# ESP8266.net
KiCad netlist of a schematic drawn in Altium Designer
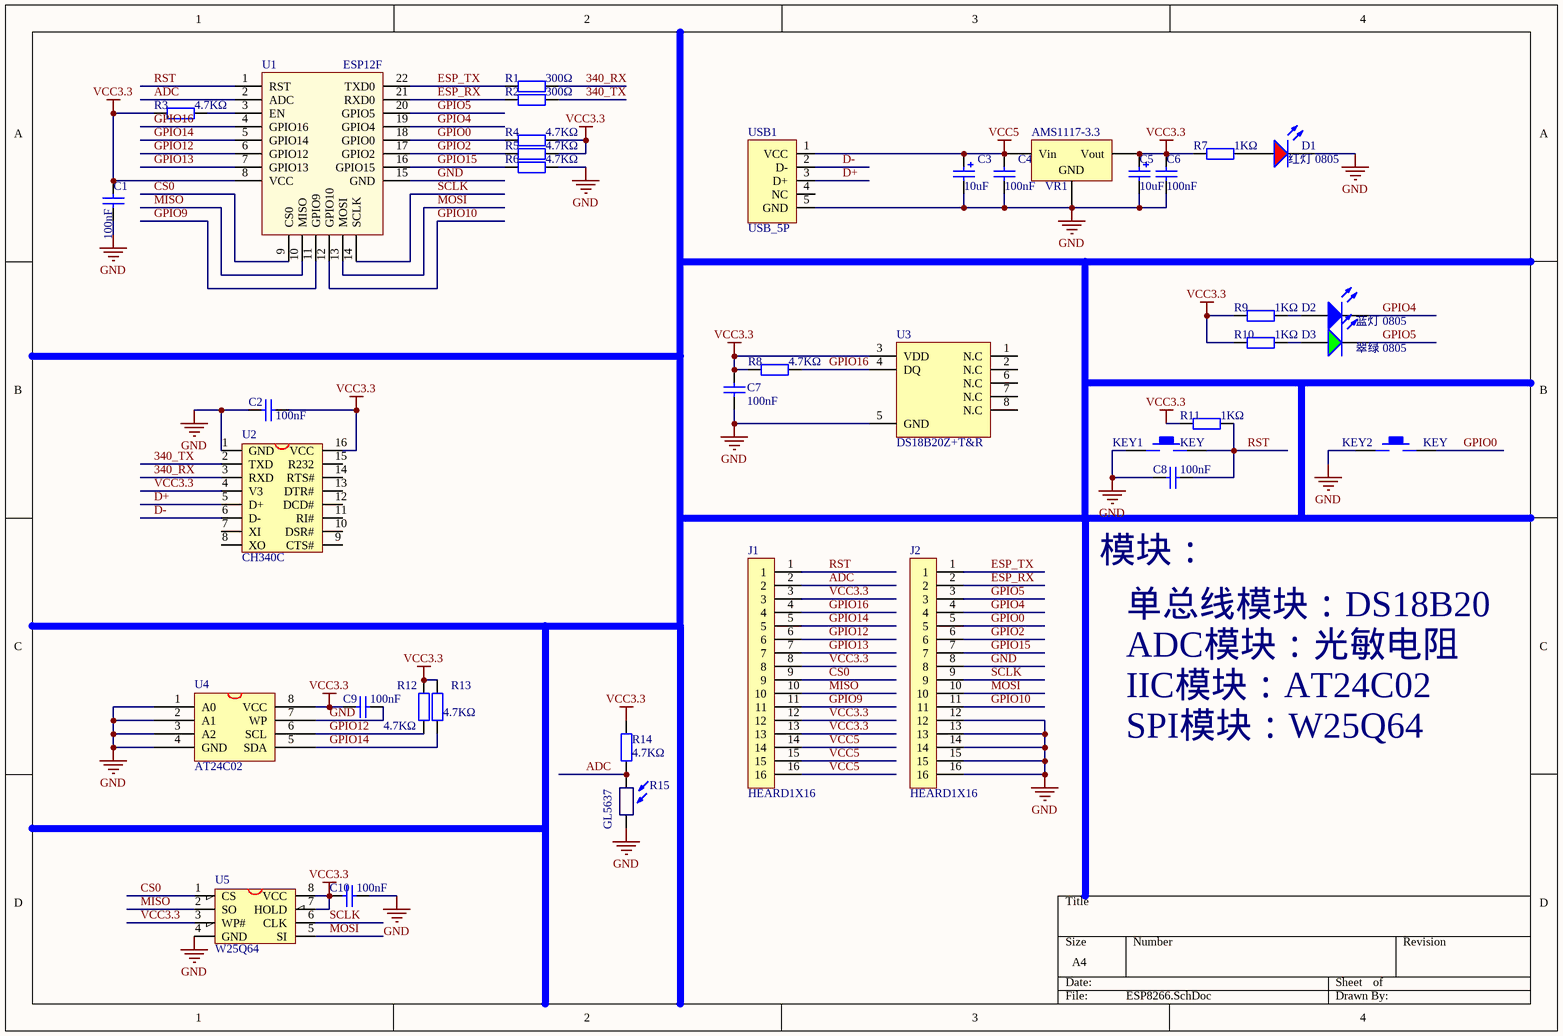
[diagram p0: ESP8266.SchDoc]

(export (version "E")
  (design (tool "Eeschema 10.0.6"))
  (components
    (comp (ref "C1")
      (value "100nF")
      (footprint "LC-0805_C")
      (description "贴片电容")
      (libsource (lib "Miscellaneous Devices LC") (part "0805 100nF(104) 10% 50V"))
    )
    (comp (ref "C2")
      (value "100nF")
      (footprint "LC-0805_C")
      (description "贴片电容")
      (libsource (lib "Miscellaneous Devices LC") (part "0805 100nF(104) 10% 50V"))
    )
    (comp (ref "C3")
      (value "10uF")
      (footprint "LC-CASE-A_3216")
      (description "钽电容")
      (libsource (lib "Miscellaneous Devices LC") (part "3216 10uF (106) 10% 16V"))
    )
    (comp (ref "C4")
      (value "100nF")
      (footprint "LC-0805_C")
      (description "贴片电容")
      (libsource (lib "Miscellaneous Devices LC") (part "0805 100nF(104) 10% 50V"))
    )
    (comp (ref "C5")
      (value "10uF")
      (footprint "LC-CASE-A_3216")
      (description "钽电容")
      (libsource (lib "Miscellaneous Devices LC") (part "3216 10uF (106) 10% 16V"))
    )
    (comp (ref "C6")
      (value "100nF")
      (footprint "LC-0805_C")
      (description "贴片电容")
      (libsource (lib "Miscellaneous Devices LC") (part "0805 100nF(104) 10% 50V"))
    )
    (comp (ref "C7")
      (value "100nF")
      (footprint "LC-0805_C")
      (description "贴片电容")
      (libsource (lib "Miscellaneous Devices LC") (part "0805 100nF(104) 10% 50V"))
    )
    (comp (ref "C8")
      (value "100nF")
      (footprint "LC-0805_C")
      (description "贴片电容")
      (libsource (lib "Miscellaneous Devices LC") (part "0805 100nF(104) 10% 50V"))
    )
    (comp (ref "C9")
      (value "100nF")
      (footprint "LC-0805_C")
      (description "贴片电容")
      (libsource (lib "Miscellaneous Devices LC") (part "0805 100nF(104) 10% 50V"))
    )
    (comp (ref "C10")
      (value "100nF")
      (footprint "LC-0805_C")
      (description "贴片电容")
      (libsource (lib "Miscellaneous Devices LC") (part "0805 100nF(104) 10% 50V"))
    )
    (comp (ref "D1")
      (value "红灯 0805")
      (footprint "LC-0805_LED_S1")
      (description "发光二极管")
      (libsource (lib "Miscellaneous Devices LC") (part "0805 红灯"))
    )
    (comp (ref "D2")
      (value "蓝灯 0805")
      (footprint "LC-0805_LED_S1")
      (description "发光二极管")
      (libsource (lib "Miscellaneous Devices LC") (part "0805 蓝灯"))
    )
    (comp (ref "D3")
      (value "翠绿 0805")
      (footprint "LC-0805_LED_S1")
      (description "发光二极管")
      (libsource (lib "Miscellaneous Devices LC") (part "0805 翠绿"))
    )
    (comp (ref "J1") (value "HEARD1X16") (footprint "HDR1X16") (libsource (lib "ESP8266") (part "HEARD1X16")))
    (comp (ref "J2") (value "HEARD1X16") (footprint "HDR1X16") (libsource (lib "ESP8266") (part "HEARD1X16")))
    (comp (ref "KEY1") (value "KEY") (footprint "KEY_直插_6*6") (libsource (lib "ESP8266") (part "KEY")))
    (comp (ref "KEY2") (value "KEY") (footprint "KEY_直插_6*6") (libsource (lib "ESP8266") (part "KEY")))
    (comp (ref "R1")
      (value "300Ω")
      (footprint "LC-0805_R")
      (description "贴片电阻")
      (libsource (lib "Miscellaneous Devices LC") (part "0805 4.7KΩ (4701) 1%"))
    )
    (comp (ref "R2")
      (value "300Ω")
      (footprint "LC-0805_R")
      (description "贴片电阻")
      (libsource (lib "Miscellaneous Devices LC") (part "0805 4.7KΩ (4701) 1%"))
    )
    (comp (ref "R3")
      (value "4.7KΩ")
      (footprint "LC-0805_R")
      (description "贴片电阻")
      (libsource (lib "Miscellaneous Devices LC") (part "0805 4.7KΩ (4701) 1%"))
    )
    (comp (ref "R4")
      (value "4.7KΩ")
      (footprint "LC-0805_R")
      (description "贴片电阻")
      (libsource (lib "Miscellaneous Devices LC") (part "0805 4.7KΩ (4701) 1%"))
    )
    (comp (ref "R5")
      (value "4.7KΩ")
      (footprint "LC-0805_R")
      (description "贴片电阻")
      (libsource (lib "Miscellaneous Devices LC") (part "0805 4.7KΩ (4701) 1%"))
    )
    (comp (ref "R6")
      (value "4.7KΩ")
      (footprint "LC-0805_R")
      (description "贴片电阻")
      (libsource (lib "Miscellaneous Devices LC") (part "0805 4.7KΩ (4701) 1%"))
    )
    (comp (ref "R7")
      (value "1KΩ")
      (footprint "LC-0805_R")
      (description "贴片电阻")
      (libsource (lib "Miscellaneous Devices LC") (part "0805 1KΩ (1001) 1%"))
    )
    (comp (ref "R8")
      (value "4.7KΩ")
      (footprint "LC-0805_R")
      (description "贴片电阻")
      (libsource (lib "Miscellaneous Devices LC") (part "0805 4.7KΩ (4701) 1%"))
    )
    (comp (ref "R9")
      (value "1KΩ")
      (footprint "LC-0805_R")
      (description "贴片电阻")
      (libsource (lib "Miscellaneous Devices LC") (part "0805 1KΩ (1001) 1%"))
    )
    (comp (ref "R10")
      (value "1KΩ")
      (footprint "LC-0805_R")
      (description "贴片电阻")
      (libsource (lib "Miscellaneous Devices LC") (part "0805 1KΩ (1001) 1%"))
    )
    (comp (ref "R11")
      (value "1KΩ")
      (footprint "LC-0805_R")
      (description "贴片电阻")
      (libsource (lib "Miscellaneous Devices LC") (part "0805 1KΩ (1001) 1%"))
    )
    (comp (ref "R12")
      (value "4.7KΩ")
      (footprint "LC-0805_R")
      (description "贴片电阻")
      (libsource (lib "") (part "0805 4.7KΩ (4701) 1%_1"))
    )
    (comp (ref "R13")
      (value "4.7KΩ")
      (footprint "LC-0805_R")
      (description "贴片电阻")
      (libsource (lib "") (part "0805 4.7KΩ (4701) 1%_1"))
    )
    (comp (ref "R14")
      (value "4.7KΩ")
      (footprint "LC-0805_R")
      (description "贴片电阻")
      (libsource (lib "") (part "0805 4.7KΩ (4701) 1%_1"))
    )
    (comp (ref "R15") (value "GL5637") (footprint "Through Hole") (libsource (lib "ESP8266") (part "GL5637")))
    (comp (ref "U1") (value "ESP12F") (footprint "ESP6266") (libsource (lib "ESP8266") (part "ESP8266")))
    (comp (ref "U2") (value "CH340C") (footprint "SOIC-16_150MIL") (libsource (lib "ESP8266") (part "CH340")))
    (comp (ref "U3")
      (value "DS18B20Z+T&R")
      (footprint "SOIC-8_150mil")
      (libsource (lib "ESP8266") (part "DS18B20Z+T&R"))
    )
    (comp (ref "U4")
      (value "AT24C02")
      (footprint "SOIC-8_150mil")
      (libsource (lib "ESP8266") (part "AT24C02"))
    )
    (comp (ref "U5") (value "W25Q64") (footprint "SOIC-8_208MIL") (libsource (lib "ESP8266") (part "W25Q64")))
    (comp (ref "USB1") (value "USB_5P") (footprint "USB_5P") (libsource (lib "ESP8266") (part "USB_5P")))
    (comp (ref "VR1")
      (value "AMS1117-3.3")
      (footprint "LC-SOT-223")
      (description "低压差线性稳压(LDO)")
      (libsource (lib "Miscellaneous Devices LC") (part "SOT-223 AMS1117-3.3"))
    )
  )
  (nets
    (net (code "1") (name "/340_RX") (class "Default")
      (node (ref "R1") (pin "2") (pinfunction "2_2") (pintype "passive"))
      (node (ref "U2") (pin "3") (pinfunction "RXD_3") (pintype "passive"))
    )
    (net (code "2") (name "/340_TX") (class "Default")
      (node (ref "R2") (pin "2") (pinfunction "2_2") (pintype "passive"))
      (node (ref "U2") (pin "2") (pinfunction "TXD_2") (pintype "passive"))
    )
    (net (code "3") (name "/ADC") (class "Default")
      (node (ref "J1") (pin "2") (pinfunction "2_2") (pintype "passive"))
      (node (ref "R14") (pin "1") (pinfunction "1_1") (pintype "passive"))
      (node (ref "R15") (pin "1") (pinfunction "1_1") (pintype "passive"))
      (node (ref "U1") (pin "2") (pinfunction "ADC_2") (pintype "passive"))
    )
    (net (code "4") (name "/CS0") (class "Default")
      (node (ref "J1") (pin "9") (pinfunction "9_9") (pintype "passive"))
      (node (ref "U1") (pin "9") (pinfunction "CS0_9") (pintype "passive"))
      (node (ref "U5") (pin "1") (pinfunction "CS_1") (pintype "passive"))
    )
    (net (code "5") (name "/D+") (class "Default")
      (node (ref "U2") (pin "5") (pinfunction "D+_5") (pintype "passive"))
      (node (ref "USB1") (pin "3") (pinfunction "D+_3") (pintype "passive"))
    )
    (net (code "6") (name "/D-") (class "Default")
      (node (ref "U2") (pin "6") (pinfunction "D-_6") (pintype "passive"))
      (node (ref "USB1") (pin "2") (pinfunction "D-_2") (pintype "passive"))
    )
    (net (code "7") (name "/ESP_RX") (class "Default")
      (node (ref "J2") (pin "2") (pinfunction "2_2") (pintype "passive"))
      (node (ref "R2") (pin "1") (pinfunction "1_1") (pintype "passive"))
      (node (ref "U1") (pin "21") (pinfunction "RXD0_21") (pintype "passive"))
    )
    (net (code "8") (name "/ESP_TX") (class "Default")
      (node (ref "J2") (pin "1") (pinfunction "1_1") (pintype "passive"))
      (node (ref "R1") (pin "1") (pinfunction "1_1") (pintype "passive"))
      (node (ref "U1") (pin "22") (pinfunction "TXD0_22") (pintype "passive"))
    )
    (net (code "9") (name "/GPIO0") (class "Default")
      (node (ref "J2") (pin "5") (pinfunction "5_5") (pintype "passive"))
      (node (ref "KEY2") (pin "2") (pinfunction "2_2") (pintype "passive"))
      (node (ref "R4") (pin "1") (pinfunction "1_1") (pintype "passive"))
      (node (ref "U1") (pin "18") (pinfunction "GPIO0_18") (pintype "passive"))
    )
    (net (code "10") (name "/GPIO2") (class "Default")
      (node (ref "J2") (pin "6") (pinfunction "6_6") (pintype "passive"))
      (node (ref "R5") (pin "1") (pinfunction "1_1") (pintype "passive"))
      (node (ref "U1") (pin "17") (pinfunction "GPIO2_17") (pintype "passive"))
    )
    (net (code "11") (name "/GPIO4") (class "Default")
      (node (ref "D2") (pin "K") (pinfunction "K_K") (pintype "passive"))
      (node (ref "J2") (pin "4") (pinfunction "4_4") (pintype "passive"))
      (node (ref "U1") (pin "19") (pinfunction "GPIO4_19") (pintype "passive"))
    )
    (net (code "12") (name "/GPIO5") (class "Default")
      (node (ref "D3") (pin "K") (pinfunction "K_K") (pintype "passive"))
      (node (ref "J2") (pin "3") (pinfunction "3_3") (pintype "passive"))
      (node (ref "U1") (pin "20") (pinfunction "GPIO5_20") (pintype "passive"))
    )
    (net (code "13") (name "/GPIO9") (class "Default")
      (node (ref "J1") (pin "11") (pinfunction "11_11") (pintype "passive"))
      (node (ref "U1") (pin "11") (pinfunction "GPIO9_11") (pintype "passive"))
    )
    (net (code "14") (name "/GPIO10") (class "Default")
      (node (ref "J2") (pin "11") (pinfunction "11_11") (pintype "passive"))
      (node (ref "U1") (pin "12") (pinfunction "GPIO10_12") (pintype "passive"))
    )
    (net (code "15") (name "/GPIO12") (class "Default")
      (node (ref "J1") (pin "6") (pinfunction "6_6") (pintype "passive"))
      (node (ref "R12") (pin "1") (pinfunction "1_1") (pintype "passive"))
      (node (ref "U1") (pin "6") (pinfunction "GPIO12_6") (pintype "passive"))
      (node (ref "U4") (pin "6") (pinfunction "SCL_6") (pintype "passive"))
    )
    (net (code "16") (name "/GPIO13") (class "Default")
      (node (ref "J1") (pin "7") (pinfunction "7_7") (pintype "passive"))
      (node (ref "U1") (pin "7") (pinfunction "GPIO13_7") (pintype "passive"))
    )
    (net (code "17") (name "/GPIO14") (class "Default")
      (node (ref "J1") (pin "5") (pinfunction "5_5") (pintype "passive"))
      (node (ref "R13") (pin "1") (pinfunction "1_1") (pintype "passive"))
      (node (ref "U1") (pin "5") (pinfunction "GPIO14_5") (pintype "passive"))
      (node (ref "U4") (pin "5") (pinfunction "SDA_5") (pintype "passive"))
    )
    (net (code "18") (name "/GPIO15") (class "Default")
      (node (ref "J2") (pin "7") (pinfunction "7_7") (pintype "passive"))
      (node (ref "R6") (pin "1") (pinfunction "1_1") (pintype "passive"))
      (node (ref "U1") (pin "16") (pinfunction "GPIO15_16") (pintype "passive"))
    )
    (net (code "19") (name "/GPIO16") (class "Default")
      (node (ref "J1") (pin "4") (pinfunction "4_4") (pintype "passive"))
      (node (ref "R8") (pin "2") (pinfunction "2_2") (pintype "passive"))
      (node (ref "U1") (pin "4") (pinfunction "GPIO16_4") (pintype "passive"))
      (node (ref "U3") (pin "4") (pinfunction "DQ_4") (pintype "passive"))
    )
    (net (code "20") (name "/MISO") (class "Default")
      (node (ref "J1") (pin "10") (pinfunction "10_10") (pintype "passive"))
      (node (ref "U1") (pin "10") (pinfunction "MISO_10") (pintype "passive"))
      (node (ref "U5") (pin "2") (pinfunction "SO_2") (pintype "passive"))
    )
    (net (code "21") (name "/MOSI") (class "Default")
      (node (ref "J2") (pin "10") (pinfunction "10_10") (pintype "passive"))
      (node (ref "U1") (pin "13") (pinfunction "MOSI_13") (pintype "passive"))
      (node (ref "U5") (pin "5") (pinfunction "SI_5") (pintype "passive"))
    )
    (net (code "22") (name "/RST") (class "Default")
      (node (ref "C8") (pin "2") (pinfunction "2_2") (pintype "passive"))
      (node (ref "J1") (pin "1") (pinfunction "1_1") (pintype "passive"))
      (node (ref "KEY1") (pin "2") (pinfunction "2_2") (pintype "passive"))
      (node (ref "R11") (pin "2") (pinfunction "2_2") (pintype "passive"))
      (node (ref "U1") (pin "1") (pinfunction "RST_1") (pintype "passive"))
    )
    (net (code "23") (name "/SCLK") (class "Default")
      (node (ref "J2") (pin "9") (pinfunction "9_9") (pintype "passive"))
      (node (ref "U1") (pin "14") (pinfunction "SCLK_14") (pintype "passive"))
      (node (ref "U5") (pin "6") (pinfunction "CLK_6") (pintype "passive"))
    )
    (net (code "24") (name "GND") (class "Default")
      (node (ref "C1") (pin "1") (pinfunction "1_1") (pintype "passive"))
      (node (ref "C10") (pin "2") (pinfunction "2_2") (pintype "passive"))
      (node (ref "C2") (pin "1") (pinfunction "1_1") (pintype "passive"))
      (node (ref "C3") (pin "2") (pinfunction "2_2") (pintype "passive"))
      (node (ref "C4") (pin "1") (pinfunction "1_1") (pintype "passive"))
      (node (ref "C5") (pin "2") (pinfunction "2_2") (pintype "passive"))
      (node (ref "C6") (pin "1") (pinfunction "1_1") (pintype "passive"))
      (node (ref "C7") (pin "1") (pinfunction "1_1") (pintype "passive"))
      (node (ref "C8") (pin "1") (pinfunction "1_1") (pintype "passive"))
      (node (ref "C9") (pin "2") (pinfunction "2_2") (pintype "passive"))
      (node (ref "D1") (pin "K") (pinfunction "K_K") (pintype "passive"))
      (node (ref "J2") (pin "12") (pinfunction "12_12") (pintype "passive"))
      (node (ref "J2") (pin "13") (pinfunction "13_13") (pintype "passive"))
      (node (ref "J2") (pin "14") (pinfunction "14_14") (pintype "passive"))
      (node (ref "J2") (pin "15") (pinfunction "15_15") (pintype "passive"))
      (node (ref "J2") (pin "16") (pinfunction "16_16") (pintype "passive"))
      (node (ref "J2") (pin "8") (pinfunction "8_8") (pintype "passive"))
      (node (ref "KEY1") (pin "1") (pinfunction "1_1") (pintype "passive"))
      (node (ref "KEY2") (pin "1") (pinfunction "1_1") (pintype "passive"))
      (node (ref "R15") (pin "2") (pinfunction "2_2") (pintype "passive"))
      (node (ref "R6") (pin "2") (pinfunction "2_2") (pintype "passive"))
      (node (ref "U1") (pin "15") (pinfunction "GND_15") (pintype "passive"))
      (node (ref "U2") (pin "1") (pinfunction "GND_1") (pintype "passive"))
      (node (ref "U3") (pin "5") (pinfunction "GND_5") (pintype "passive"))
      (node (ref "U4") (pin "1") (pinfunction "A0_1") (pintype "passive"))
      (node (ref "U4") (pin "2") (pinfunction "A1_2") (pintype "passive"))
      (node (ref "U4") (pin "3") (pinfunction "A2_3") (pintype "passive"))
      (node (ref "U4") (pin "4") (pinfunction "GND_4") (pintype "passive"))
      (node (ref "U4") (pin "7") (pinfunction "WP_7") (pintype "passive"))
      (node (ref "U5") (pin "4") (pinfunction "GND_4") (pintype "passive"))
      (node (ref "USB1") (pin "5") (pinfunction "GND_5") (pintype "passive"))
      (node (ref "VR1") (pin "1") (pinfunction "GND_1") (pintype "passive"))
    )
    (net (code "25") (name "Net-(D1-PadA)") (class "Default")
      (node (ref "D1") (pin "A") (pinfunction "A_A") (pintype "passive"))
      (node (ref "R7") (pin "2") (pinfunction "2_2") (pintype "passive"))
    )
    (net (code "26") (name "Net-(D2-PadA)") (class "Default")
      (node (ref "D2") (pin "A") (pinfunction "A_A") (pintype "passive"))
      (node (ref "R9") (pin "2") (pinfunction "2_2") (pintype "passive"))
    )
    (net (code "27") (name "Net-(D3-PadA)") (class "Default")
      (node (ref "D3") (pin "A") (pinfunction "A_A") (pintype "passive"))
      (node (ref "R10") (pin "2") (pinfunction "2_2") (pintype "passive"))
    )
    (net (code "28") (name "Net-(U1-EN)") (class "Default")
      (node (ref "R3") (pin "2") (pinfunction "2_2") (pintype "passive"))
      (node (ref "U1") (pin "3") (pinfunction "EN_3") (pintype "passive"))
    )
    (net (code "29") (name "VCC3.3") (class "Default")
      (node (ref "C1") (pin "2") (pinfunction "2_2") (pintype "passive"))
      (node (ref "C10") (pin "1") (pinfunction "1_1") (pintype "passive"))
      (node (ref "C2") (pin "2") (pinfunction "2_2") (pintype "passive"))
      (node (ref "C5") (pin "1") (pinfunction "1_1") (pintype "passive"))
      (node (ref "C6") (pin "2") (pinfunction "2_2") (pintype "passive"))
      (node (ref "C7") (pin "2") (pinfunction "2_2") (pintype "passive"))
      (node (ref "C9") (pin "1") (pinfunction "1_1") (pintype "passive"))
      (node (ref "J1") (pin "12") (pinfunction "12_12") (pintype "passive"))
      (node (ref "J1") (pin "13") (pinfunction "13_13") (pintype "passive"))
      (node (ref "J1") (pin "3") (pinfunction "3_3") (pintype "passive"))
      (node (ref "J1") (pin "8") (pinfunction "8_8") (pintype "passive"))
      (node (ref "R10") (pin "1") (pinfunction "1_1") (pintype "passive"))
      (node (ref "R11") (pin "1") (pinfunction "1_1") (pintype "passive"))
      (node (ref "R12") (pin "2") (pinfunction "2_2") (pintype "passive"))
      (node (ref "R13") (pin "2") (pinfunction "2_2") (pintype "passive"))
      (node (ref "R14") (pin "2") (pinfunction "2_2") (pintype "passive"))
      (node (ref "R3") (pin "1") (pinfunction "1_1") (pintype "passive"))
      (node (ref "R4") (pin "2") (pinfunction "2_2") (pintype "passive"))
      (node (ref "R5") (pin "2") (pinfunction "2_2") (pintype "passive"))
      (node (ref "R7") (pin "1") (pinfunction "1_1") (pintype "passive"))
      (node (ref "R8") (pin "1") (pinfunction "1_1") (pintype "passive"))
      (node (ref "R9") (pin "1") (pinfunction "1_1") (pintype "passive"))
      (node (ref "U1") (pin "8") (pinfunction "VCC_8") (pintype "passive"))
      (node (ref "U2") (pin "16") (pinfunction "VCC_16") (pintype "passive"))
      (node (ref "U2") (pin "4") (pinfunction "V3_4") (pintype "passive"))
      (node (ref "U3") (pin "3") (pinfunction "VDD_3") (pintype "passive"))
      (node (ref "U4") (pin "8") (pinfunction "VCC_8") (pintype "passive"))
      (node (ref "U5") (pin "3") (pinfunction "WP#_3") (pintype "passive"))
      (node (ref "U5") (pin "7") (pinfunction "HOLD_7") (pintype "passive"))
      (node (ref "U5") (pin "8") (pinfunction "VCC_8") (pintype "passive"))
      (node (ref "VR1") (pin "2") (pinfunction "Vout_2") (pintype "passive"))
    )
    (net (code "30") (name "VCC5") (class "Default")
      (node (ref "C3") (pin "1") (pinfunction "1_1") (pintype "passive"))
      (node (ref "C4") (pin "2") (pinfunction "2_2") (pintype "passive"))
      (node (ref "J1") (pin "14") (pinfunction "14_14") (pintype "passive"))
      (node (ref "J1") (pin "15") (pinfunction "15_15") (pintype "passive"))
      (node (ref "J1") (pin "16") (pinfunction "16_16") (pintype "passive"))
      (node (ref "USB1") (pin "1") (pinfunction "VCC_1") (pintype "passive"))
      (node (ref "VR1") (pin "3") (pinfunction "Vin_3") (pintype "passive"))
    )
    (net (code "31") (name "unconnected-(U2-CTS#-Pad9)") (class "Default")
      (node (ref "U2") (pin "9") (pinfunction "CTS#_9") (pintype "passive"))
    )
    (net (code "32") (name "unconnected-(U2-DCD#-Pad12)") (class "Default")
      (node (ref "U2") (pin "12") (pinfunction "DCD#_12") (pintype "passive"))
    )
    (net (code "33") (name "unconnected-(U2-DSR#-Pad10)") (class "Default")
      (node (ref "U2") (pin "10") (pinfunction "DSR#_10") (pintype "passive"))
    )
    (net (code "34") (name "unconnected-(U2-DTR#-Pad13)") (class "Default")
      (node (ref "U2") (pin "13") (pinfunction "DTR#_13") (pintype "passive"))
    )
    (net (code "35") (name "unconnected-(U2-R232-Pad15)") (class "Default")
      (node (ref "U2") (pin "15") (pinfunction "R232_15") (pintype "passive"))
    )
    (net (code "36") (name "unconnected-(U2-RI#-Pad11)") (class "Default")
      (node (ref "U2") (pin "11") (pinfunction "RI#_11") (pintype "passive"))
    )
    (net (code "37") (name "unconnected-(U2-RTS#-Pad14)") (class "Default")
      (node (ref "U2") (pin "14") (pinfunction "RTS#_14") (pintype "passive"))
    )
    (net (code "38") (name "unconnected-(U2-XI-Pad7)") (class "Default")
      (node (ref "U2") (pin "7") (pinfunction "XI_7") (pintype "passive"))
    )
    (net (code "39") (name "unconnected-(U2-XO-Pad8)") (class "Default")
      (node (ref "U2") (pin "8") (pinfunction "XO_8") (pintype "passive"))
    )
    (net (code "40") (name "unconnected-(U3-N.C-Pad1)") (class "Default")
      (node (ref "U3") (pin "1") (pinfunction "N.C_1") (pintype "passive"))
    )
    (net (code "41") (name "unconnected-(U3-N.C-Pad2)") (class "Default")
      (node (ref "U3") (pin "2") (pinfunction "N.C_2") (pintype "passive"))
    )
    (net (code "42") (name "unconnected-(U3-N.C-Pad6)") (class "Default")
      (node (ref "U3") (pin "6") (pinfunction "N.C_6") (pintype "passive"))
    )
    (net (code "43") (name "unconnected-(U3-N.C-Pad7)") (class "Default")
      (node (ref "U3") (pin "7") (pinfunction "N.C_7") (pintype "passive"))
    )
    (net (code "44") (name "unconnected-(U3-N.C-Pad8)") (class "Default")
      (node (ref "U3") (pin "8") (pinfunction "N.C_8") (pintype "passive"))
    )
    (net (code "45") (name "unconnected-(USB1-NC-Pad4)") (class "Default")
      (node (ref "USB1") (pin "4") (pinfunction "NC_4") (pintype "passive"))
    )
  )
)
